# Roll_Swarm.net
KiCad netlist of a schematic drawn in EAGLE
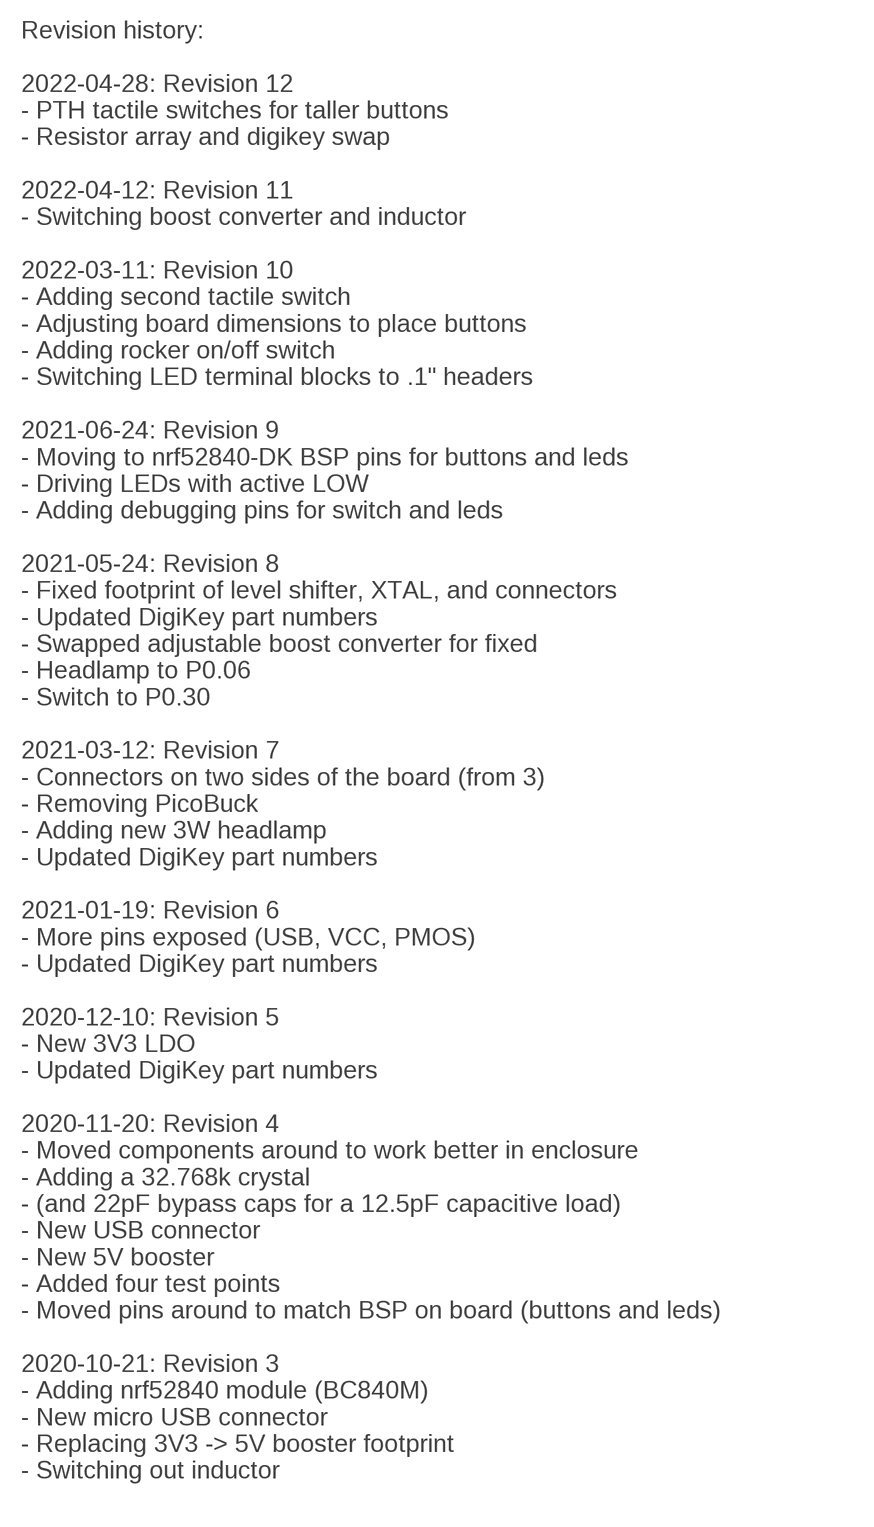
[diagram p0: schematic, sheet 1, part 1 of 2]
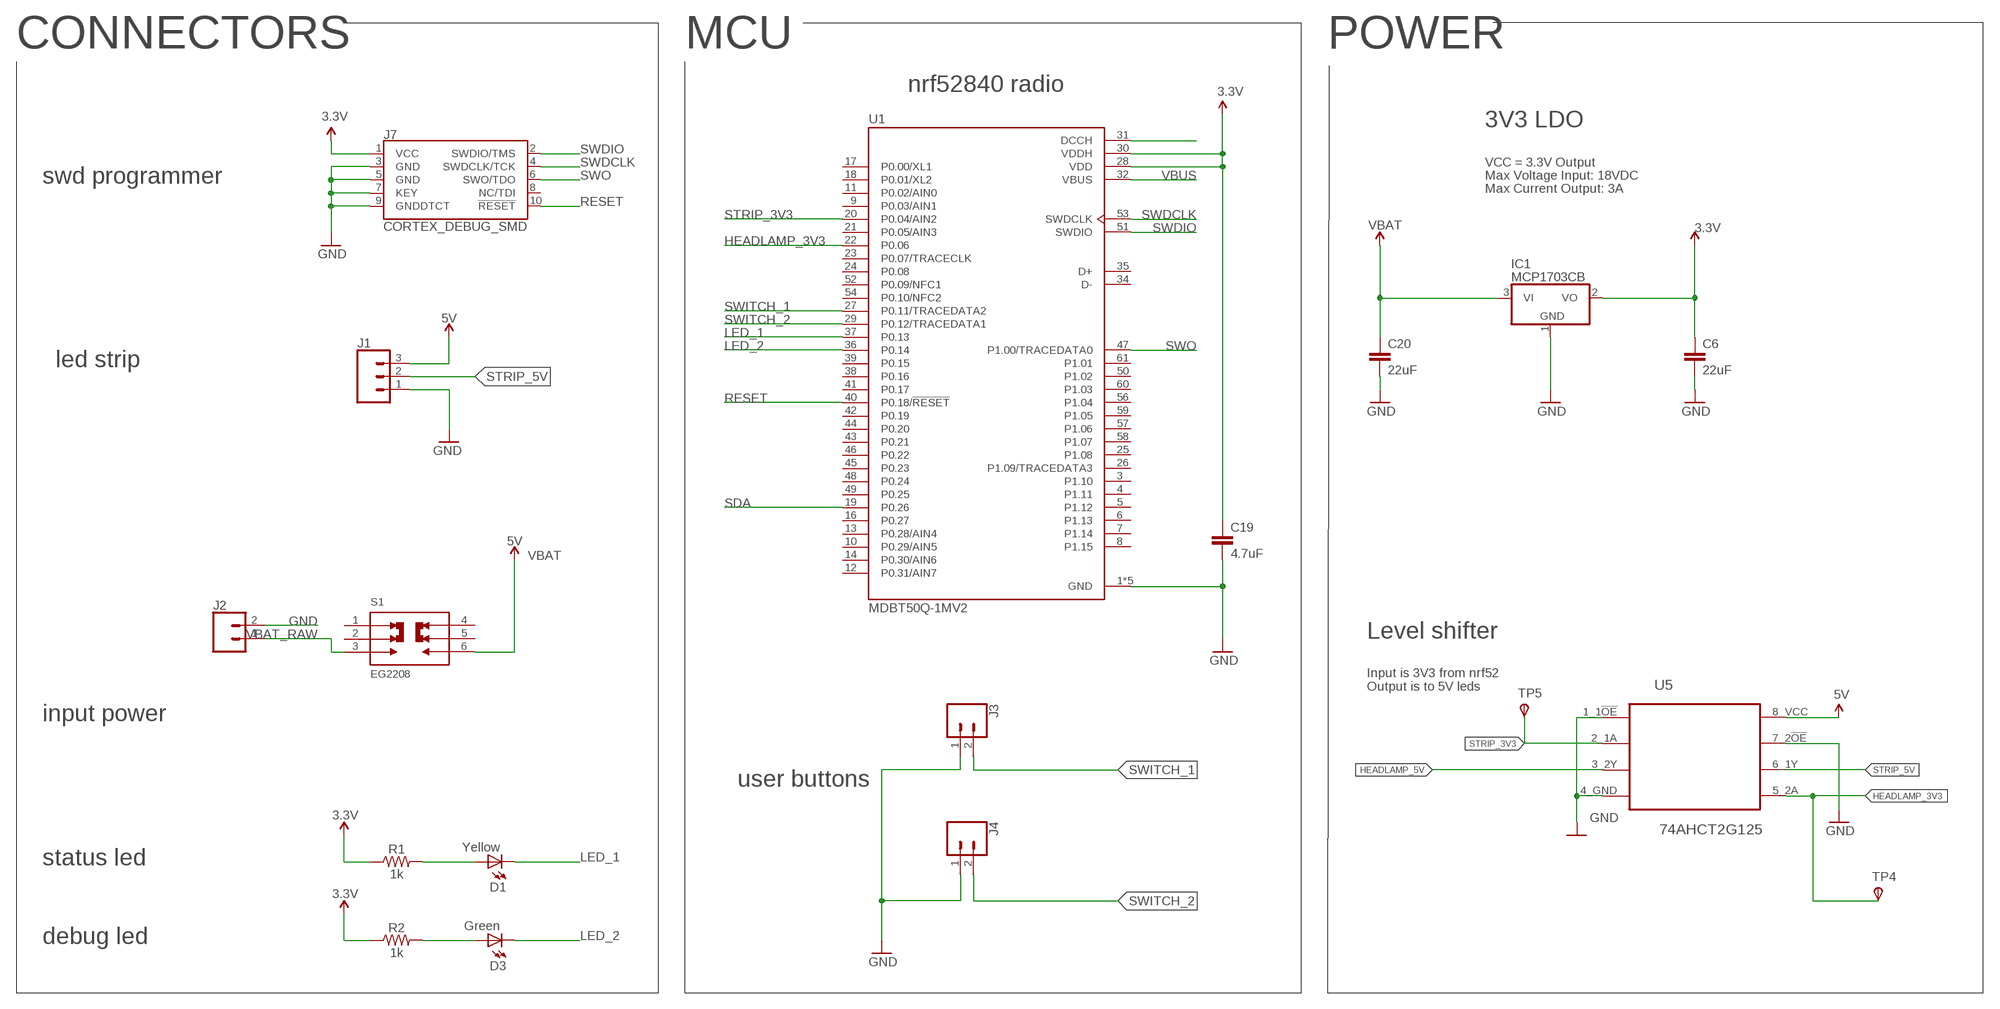
[diagram p1: schematic, sheet 1, part 2 of 2]

(export (version "E")
  (design (tool "Eeschema 10.0.6"))
  (components
    (comp (ref "C6")
      (value "22uF")
      (footprint "eagle-import:0805")
      (libsource (lib "eagle-import") (part "22UF-0805-6.3V-20%"))
    )
    (comp (ref "C19")
      (value "4.7uF")
      (footprint "eagle-import:0603")
      (libsource (lib "eagle-import") (part "4.7UF0603"))
    )
    (comp (ref "C20")
      (value "22uF")
      (footprint "eagle-import:0805")
      (libsource (lib "eagle-import") (part "22UF-0805-6.3V-20%"))
    )
    (comp (ref "D1")
      (value "Yellow")
      (footprint "eagle-import:LED-0603")
      (libsource (lib "eagle-import") (part "LED0603"))
    )
    (comp (ref "D3")
      (value "Green")
      (footprint "eagle-import:LED-0603")
      (libsource (lib "eagle-import") (part "LED0603"))
    )
    (comp (ref "IC1")
      (value "MCP1703CB")
      (footprint "eagle-import:SOT23")
      (libsource (lib "eagle-import") (part "MCP1703CB"))
    )
    (comp (ref "J1")
      (value "CONN_03LOCK_LONGPADS")
      (footprint "eagle-import:1X03_LOCK_LONGPADS")
      (libsource (lib "eagle-import") (part "CONN_03LOCK_LONGPADS"))
    )
    (comp (ref "J2")
      (value "CONN_02LOCK_LONGPADS")
      (footprint "eagle-import:1X02_LOCK_LONGPADS")
      (libsource (lib "eagle-import") (part "CONN_02LOCK_LONGPADS"))
    )
    (comp (ref "J3")
      (value "CONN_02PTH4")
      (footprint "eagle-import:1X02_XTRA_BIG")
      (libsource (lib "eagle-import") (part "CONN_02PTH4"))
    )
    (comp (ref "J4")
      (value "CONN_02PTH4")
      (footprint "eagle-import:1X02_XTRA_BIG")
      (libsource (lib "eagle-import") (part "CONN_02PTH4"))
    )
    (comp (ref "J7")
      (value "CORTEX_DEBUG_SMD")
      (footprint "eagle-import:SAMTECH_FTSH-105-01")
      (libsource (lib "eagle-import") (part "CORTEX_DEBUG_SMD"))
    )
    (comp (ref "R1")
      (value "1k")
      (footprint "eagle-import:0603")
      (libsource (lib "eagle-import") (part "1KOHM-0603-1/10W-1%"))
    )
    (comp (ref "R2")
      (value "1k")
      (footprint "eagle-import:0603")
      (libsource (lib "eagle-import") (part "1KOHM-0603-1/10W-1%"))
    )
    (comp (ref "S1")
      (value "EG2208")
      (footprint "eagle-import:SW_EG2208")
      (fields (field (name "MF") "E-Switch"))
      (libsource (lib "eagle-import") (part "EG2208"))
    )
    (comp (ref "TP4")
      (value "TPSB1,27")
      (footprint "eagle-import:B1,27")
      (libsource (lib "eagle-import") (part "TPSB1,27"))
    )
    (comp (ref "TP5")
      (value "TPSB1,27")
      (footprint "eagle-import:B1,27")
      (libsource (lib "eagle-import") (part "TPSB1,27"))
    )
    (comp (ref "U1")
      (value "MDBT50Q-1MV2")
      (footprint "eagle-import:XCVR_MDBT50Q-1MV2")
      (fields (field (name "MF") "Raytac Corporation"))
      (libsource (lib "eagle-import") (part "MDBT50Q-1MV2"))
    )
    (comp (ref "U5")
      (value "74AHCT2G125")
      (footprint "eagle-import:VSSOP-8")
      (fields (field (name "MPN") "PCA9306DC,125"))
      (libsource (lib "eagle-import") (part "VSSOP-8_DEVICE"))
    )
  )
  (nets
    (net (code "1") (name "/LED_1") (class "Default")
      (node (ref "D1") (pin "C") (pinfunction "C_C") (pintype "passive"))
      (node (ref "U1") (pin "37") (pinfunction "P0.13_37") (pintype "bidirectional"))
    )
    (net (code "2") (name "/LED_2") (class "Default")
      (node (ref "D3") (pin "C") (pinfunction "C_C") (pintype "passive"))
      (node (ref "U1") (pin "36") (pinfunction "P0.14_36") (pintype "bidirectional"))
    )
    (net (code "3") (name "/RESET") (class "Default")
      (node (ref "J7") (pin "10") (pinfunction "~{RESET}_10") (pintype "bidirectional"))
      (node (ref "U1") (pin "40") (pinfunction "P0.18/~{RESET}_40") (pintype "bidirectional"))
    )
    (net (code "4") (name "/SDA") (class "Default")
      (node (ref "U1") (pin "19") (pinfunction "P0.26_19") (pintype "bidirectional"))
    )
    (net (code "5") (name "/SWDCLK") (class "Default")
      (node (ref "J7") (pin "4") (pinfunction "SWDCLK/TCK_4") (pintype "bidirectional"))
      (node (ref "U1") (pin "53") (pinfunction "SWDCLK_53") (pintype "input"))
    )
    (net (code "6") (name "/SWDIO") (class "Default")
      (node (ref "J7") (pin "2") (pinfunction "SWDIO/TMS_2") (pintype "bidirectional"))
      (node (ref "U1") (pin "51") (pinfunction "SWDIO_51") (pintype "bidirectional"))
    )
    (net (code "7") (name "/SWO") (class "Default")
      (node (ref "J7") (pin "6") (pinfunction "SWO/TDO_6") (pintype "bidirectional"))
      (node (ref "U1") (pin "47") (pinfunction "P1.00/TRACEDATA0_47") (pintype "bidirectional"))
    )
    (net (code "8") (name "/VBAT_RAW") (class "Default")
      (node (ref "J2") (pin "1") (pinfunction "1_1") (pintype "passive"))
      (node (ref "S1") (pin "3") (pinfunction "3_3") (pintype "passive"))
    )
    (net (code "9") (name "/VBUS") (class "Default")
      (node (ref "U1") (pin "32") (pinfunction "VBUS_32") (pintype "power_in"))
    )
    (net (code "10") (name "3.3V") (class "Default")
      (node (ref "C19") (pin "1") (pinfunction "1_1") (pintype "passive"))
      (node (ref "C6") (pin "1") (pinfunction "1_1") (pintype "passive"))
      (node (ref "IC1") (pin "2") (pinfunction "VO_2") (pintype "passive"))
      (node (ref "J7") (pin "1") (pinfunction "VCC_1") (pintype "bidirectional"))
      (node (ref "R1") (pin "1") (pinfunction "1_1") (pintype "passive"))
      (node (ref "R2") (pin "1") (pinfunction "1_1") (pintype "passive"))
      (node (ref "U1") (pin "28") (pinfunction "VDD_28") (pintype "power_in"))
      (node (ref "U1") (pin "30") (pinfunction "VDDH_30") (pintype "power_in"))
    )
    (net (code "11") (name "5V") (class "Default")
      (node (ref "C20") (pin "1") (pinfunction "1_1") (pintype "passive"))
      (node (ref "IC1") (pin "3") (pinfunction "VI_3") (pintype "input"))
      (node (ref "J1") (pin "3") (pinfunction "3_3") (pintype "passive"))
      (node (ref "S1") (pin "6") (pinfunction "6_6") (pintype "passive"))
      (node (ref "U5") (pin "8_VCC") (pinfunction "8_8_VCC") (pintype "bidirectional"))
    )
    (net (code "12") (name "GND") (class "Default")
      (node (ref "C19") (pin "2") (pinfunction "2_2") (pintype "passive"))
      (node (ref "C20") (pin "2") (pinfunction "2_2") (pintype "passive"))
      (node (ref "C6") (pin "2") (pinfunction "2_2") (pintype "passive"))
      (node (ref "IC1") (pin "1") (pinfunction "GND_1") (pintype "passive"))
      (node (ref "J1") (pin "1") (pinfunction "1_1") (pintype "passive"))
      (node (ref "J2") (pin "2") (pinfunction "2_2") (pintype "passive"))
      (node (ref "J3") (pin "1") (pinfunction "1_1") (pintype "passive"))
      (node (ref "J4") (pin "1") (pinfunction "1_1") (pintype "passive"))
      (node (ref "J7") (pin "3") (pinfunction "GND_3") (pintype "bidirectional"))
      (node (ref "J7") (pin "5") (pinfunction "GND_5") (pintype "bidirectional"))
      (node (ref "J7") (pin "7") (pinfunction "KEY_7") (pintype "bidirectional"))
      (node (ref "J7") (pin "9") (pinfunction "GNDDTCT_9") (pintype "bidirectional"))
      (node (ref "U1") (pin "1") (pinfunction "GND_1") (pintype "power_in"))
      (node (ref "U1") (pin "15") (pinfunction "GND_15") (pintype "power_in"))
      (node (ref "U1") (pin "2") (pinfunction "GND_2") (pintype "power_in"))
      (node (ref "U1") (pin "33") (pinfunction "GND_33") (pintype "power_in"))
      (node (ref "U1") (pin "55") (pinfunction "GND_55") (pintype "power_in"))
      (node (ref "U5") (pin "1_1!OE") (pinfunction "1_1_1!OE") (pintype "bidirectional"))
      (node (ref "U5") (pin "4_GND") (pinfunction "4_4_GND") (pintype "bidirectional"))
      (node (ref "U5") (pin "7_2!OE") (pinfunction "7_7_2!OE") (pintype "bidirectional"))
    )
    (net (code "13") (name "HEADLAMP_3V3") (class "Default")
      (node (ref "TP4") (pin "TP") (pinfunction "PP_TP") (pintype "input"))
      (node (ref "U1") (pin "22") (pinfunction "P0.06_22") (pintype "bidirectional"))
      (node (ref "U5") (pin "5_2A") (pinfunction "5_5_2A") (pintype "bidirectional"))
    )
    (net (code "14") (name "HEADLAMP_5V") (class "Default")
      (node (ref "U5") (pin "3_2Y") (pinfunction "3_3_2Y") (pintype "bidirectional"))
    )
    (net (code "15") (name "Net-(D1-PadA)") (class "Default")
      (node (ref "D1") (pin "A") (pinfunction "A_A") (pintype "passive"))
      (node (ref "R1") (pin "2") (pinfunction "2_2") (pintype "passive"))
    )
    (net (code "16") (name "Net-(D3-PadA)") (class "Default")
      (node (ref "D3") (pin "A") (pinfunction "A_A") (pintype "passive"))
      (node (ref "R2") (pin "2") (pinfunction "2_2") (pintype "passive"))
    )
    (net (code "17") (name "STRIP_3V3") (class "Default")
      (node (ref "TP5") (pin "TP") (pinfunction "PP_TP") (pintype "input"))
      (node (ref "U1") (pin "20") (pinfunction "P0.04/AIN2_20") (pintype "bidirectional"))
      (node (ref "U5") (pin "2_1A") (pinfunction "2_2_1A") (pintype "bidirectional"))
    )
    (net (code "18") (name "STRIP_5V") (class "Default")
      (node (ref "J1") (pin "2") (pinfunction "2_2") (pintype "passive"))
      (node (ref "U5") (pin "6_1Y") (pinfunction "6_6_1Y") (pintype "bidirectional"))
    )
    (net (code "19") (name "SWITCH_1") (class "Default")
      (node (ref "J3") (pin "2") (pinfunction "2_2") (pintype "passive"))
      (node (ref "U1") (pin "27") (pinfunction "P0.11/TRACEDATA2_27") (pintype "bidirectional"))
    )
    (net (code "20") (name "SWITCH_2") (class "Default")
      (node (ref "J4") (pin "2") (pinfunction "2_2") (pintype "passive"))
      (node (ref "U1") (pin "29") (pinfunction "P0.12/TRACEDATA1_29") (pintype "bidirectional"))
    )
    (net (code "21") (name "unconnected-(J7-NC{slash}TDI-Pad8)") (class "Default")
      (node (ref "J7") (pin "8") (pinfunction "NC/TDI_8") (pintype "bidirectional"))
    )
    (net (code "22") (name "unconnected-(S1-Pad1)") (class "Default")
      (node (ref "S1") (pin "1") (pinfunction "1_1") (pintype "passive"))
    )
    (net (code "23") (name "unconnected-(S1-Pad2)") (class "Default")
      (node (ref "S1") (pin "2") (pinfunction "2_2") (pintype "passive"))
    )
    (net (code "24") (name "unconnected-(S1-Pad4)") (class "Default")
      (node (ref "S1") (pin "4") (pinfunction "4_4") (pintype "passive"))
    )
    (net (code "25") (name "unconnected-(S1-Pad5)") (class "Default")
      (node (ref "S1") (pin "5") (pinfunction "5_5") (pintype "passive"))
    )
    (net (code "26") (name "unconnected-(U1-D+-Pad35)") (class "Default")
      (node (ref "U1") (pin "35") (pinfunction "D+_35") (pintype "bidirectional"))
    )
    (net (code "27") (name "unconnected-(U1-D--Pad34)") (class "Default")
      (node (ref "U1") (pin "34") (pinfunction "D-_34") (pintype "bidirectional"))
    )
    (net (code "28") (name "unconnected-(U1-DCCH-Pad31)") (class "Default")
      (node (ref "U1") (pin "31") (pinfunction "DCCH_31") (pintype "power_in"))
    )
    (net (code "29") (name "unconnected-(U1-P0.00{slash}XL1-Pad17)") (class "Default")
      (node (ref "U1") (pin "17") (pinfunction "P0.00/XL1_17") (pintype "bidirectional"))
    )
    (net (code "30") (name "unconnected-(U1-P0.01{slash}XL2-Pad18)") (class "Default")
      (node (ref "U1") (pin "18") (pinfunction "P0.01/XL2_18") (pintype "bidirectional"))
    )
    (net (code "31") (name "unconnected-(U1-P0.02{slash}AIN0-Pad11)") (class "Default")
      (node (ref "U1") (pin "11") (pinfunction "P0.02/AIN0_11") (pintype "bidirectional"))
    )
    (net (code "32") (name "unconnected-(U1-P0.03{slash}AIN1-Pad9)") (class "Default")
      (node (ref "U1") (pin "9") (pinfunction "P0.03/AIN1_9") (pintype "bidirectional"))
    )
    (net (code "33") (name "unconnected-(U1-P0.05{slash}AIN3-Pad21)") (class "Default")
      (node (ref "U1") (pin "21") (pinfunction "P0.05/AIN3_21") (pintype "bidirectional"))
    )
    (net (code "34") (name "unconnected-(U1-P0.07{slash}TRACECLK-Pad23)") (class "Default")
      (node (ref "U1") (pin "23") (pinfunction "P0.07/TRACECLK_23") (pintype "bidirectional"))
    )
    (net (code "35") (name "unconnected-(U1-P0.08-Pad24)") (class "Default")
      (node (ref "U1") (pin "24") (pinfunction "P0.08_24") (pintype "bidirectional"))
    )
    (net (code "36") (name "unconnected-(U1-P0.09{slash}NFC1-Pad52)") (class "Default")
      (node (ref "U1") (pin "52") (pinfunction "P0.09/NFC1_52") (pintype "bidirectional"))
    )
    (net (code "37") (name "unconnected-(U1-P0.10{slash}NFC2-Pad54)") (class "Default")
      (node (ref "U1") (pin "54") (pinfunction "P0.10/NFC2_54") (pintype "bidirectional"))
    )
    (net (code "38") (name "unconnected-(U1-P0.15-Pad39)") (class "Default")
      (node (ref "U1") (pin "39") (pinfunction "P0.15_39") (pintype "bidirectional"))
    )
    (net (code "39") (name "unconnected-(U1-P0.16-Pad38)") (class "Default")
      (node (ref "U1") (pin "38") (pinfunction "P0.16_38") (pintype "bidirectional"))
    )
    (net (code "40") (name "unconnected-(U1-P0.17-Pad41)") (class "Default")
      (node (ref "U1") (pin "41") (pinfunction "P0.17_41") (pintype "bidirectional"))
    )
    (net (code "41") (name "unconnected-(U1-P0.19-Pad42)") (class "Default")
      (node (ref "U1") (pin "42") (pinfunction "P0.19_42") (pintype "bidirectional"))
    )
    (net (code "42") (name "unconnected-(U1-P0.20-Pad44)") (class "Default")
      (node (ref "U1") (pin "44") (pinfunction "P0.20_44") (pintype "bidirectional"))
    )
    (net (code "43") (name "unconnected-(U1-P0.21-Pad43)") (class "Default")
      (node (ref "U1") (pin "43") (pinfunction "P0.21_43") (pintype "bidirectional"))
    )
    (net (code "44") (name "unconnected-(U1-P0.22-Pad46)") (class "Default")
      (node (ref "U1") (pin "46") (pinfunction "P0.22_46") (pintype "bidirectional"))
    )
    (net (code "45") (name "unconnected-(U1-P0.23-Pad45)") (class "Default")
      (node (ref "U1") (pin "45") (pinfunction "P0.23_45") (pintype "bidirectional"))
    )
    (net (code "46") (name "unconnected-(U1-P0.24-Pad48)") (class "Default")
      (node (ref "U1") (pin "48") (pinfunction "P0.24_48") (pintype "bidirectional"))
    )
    (net (code "47") (name "unconnected-(U1-P0.25-Pad49)") (class "Default")
      (node (ref "U1") (pin "49") (pinfunction "P0.25_49") (pintype "bidirectional"))
    )
    (net (code "48") (name "unconnected-(U1-P0.27-Pad16)") (class "Default")
      (node (ref "U1") (pin "16") (pinfunction "P0.27_16") (pintype "bidirectional"))
    )
    (net (code "49") (name "unconnected-(U1-P0.28{slash}AIN4-Pad13)") (class "Default")
      (node (ref "U1") (pin "13") (pinfunction "P0.28/AIN4_13") (pintype "bidirectional"))
    )
    (net (code "50") (name "unconnected-(U1-P0.29{slash}AIN5-Pad10)") (class "Default")
      (node (ref "U1") (pin "10") (pinfunction "P0.29/AIN5_10") (pintype "bidirectional"))
    )
    (net (code "51") (name "unconnected-(U1-P0.30{slash}AIN6-Pad14)") (class "Default")
      (node (ref "U1") (pin "14") (pinfunction "P0.30/AIN6_14") (pintype "bidirectional"))
    )
    (net (code "52") (name "unconnected-(U1-P0.31{slash}AIN7-Pad12)") (class "Default")
      (node (ref "U1") (pin "12") (pinfunction "P0.31/AIN7_12") (pintype "bidirectional"))
    )
    (net (code "53") (name "unconnected-(U1-P1.01-Pad61)") (class "Default")
      (node (ref "U1") (pin "61") (pinfunction "P1.01_61") (pintype "bidirectional"))
    )
    (net (code "54") (name "unconnected-(U1-P1.02-Pad50)") (class "Default")
      (node (ref "U1") (pin "50") (pinfunction "P1.02_50") (pintype "bidirectional"))
    )
    (net (code "55") (name "unconnected-(U1-P1.03-Pad60)") (class "Default")
      (node (ref "U1") (pin "60") (pinfunction "P1.03_60") (pintype "bidirectional"))
    )
    (net (code "56") (name "unconnected-(U1-P1.04-Pad56)") (class "Default")
      (node (ref "U1") (pin "56") (pinfunction "P1.04_56") (pintype "bidirectional"))
    )
    (net (code "57") (name "unconnected-(U1-P1.05-Pad59)") (class "Default")
      (node (ref "U1") (pin "59") (pinfunction "P1.05_59") (pintype "bidirectional"))
    )
    (net (code "58") (name "unconnected-(U1-P1.06-Pad57)") (class "Default")
      (node (ref "U1") (pin "57") (pinfunction "P1.06_57") (pintype "bidirectional"))
    )
    (net (code "59") (name "unconnected-(U1-P1.07-Pad58)") (class "Default")
      (node (ref "U1") (pin "58") (pinfunction "P1.07_58") (pintype "bidirectional"))
    )
    (net (code "60") (name "unconnected-(U1-P1.08-Pad25)") (class "Default")
      (node (ref "U1") (pin "25") (pinfunction "P1.08_25") (pintype "bidirectional"))
    )
    (net (code "61") (name "unconnected-(U1-P1.09{slash}TRACEDATA3-Pad26)") (class "Default")
      (node (ref "U1") (pin "26") (pinfunction "P1.09/TRACEDATA3_26") (pintype "bidirectional"))
    )
    (net (code "62") (name "unconnected-(U1-P1.10-Pad3)") (class "Default")
      (node (ref "U1") (pin "3") (pinfunction "P1.10_3") (pintype "bidirectional"))
    )
    (net (code "63") (name "unconnected-(U1-P1.11-Pad4)") (class "Default")
      (node (ref "U1") (pin "4") (pinfunction "P1.11_4") (pintype "bidirectional"))
    )
    (net (code "64") (name "unconnected-(U1-P1.12-Pad5)") (class "Default")
      (node (ref "U1") (pin "5") (pinfunction "P1.12_5") (pintype "bidirectional"))
    )
    (net (code "65") (name "unconnected-(U1-P1.13-Pad6)") (class "Default")
      (node (ref "U1") (pin "6") (pinfunction "P1.13_6") (pintype "bidirectional"))
    )
    (net (code "66") (name "unconnected-(U1-P1.14-Pad7)") (class "Default")
      (node (ref "U1") (pin "7") (pinfunction "P1.14_7") (pintype "bidirectional"))
    )
    (net (code "67") (name "unconnected-(U1-P1.15-Pad8)") (class "Default")
      (node (ref "U1") (pin "8") (pinfunction "P1.15_8") (pintype "bidirectional"))
    )
  )
)
